# Tally_v01.net
KiCad netlist of a schematic drawn in EAGLE
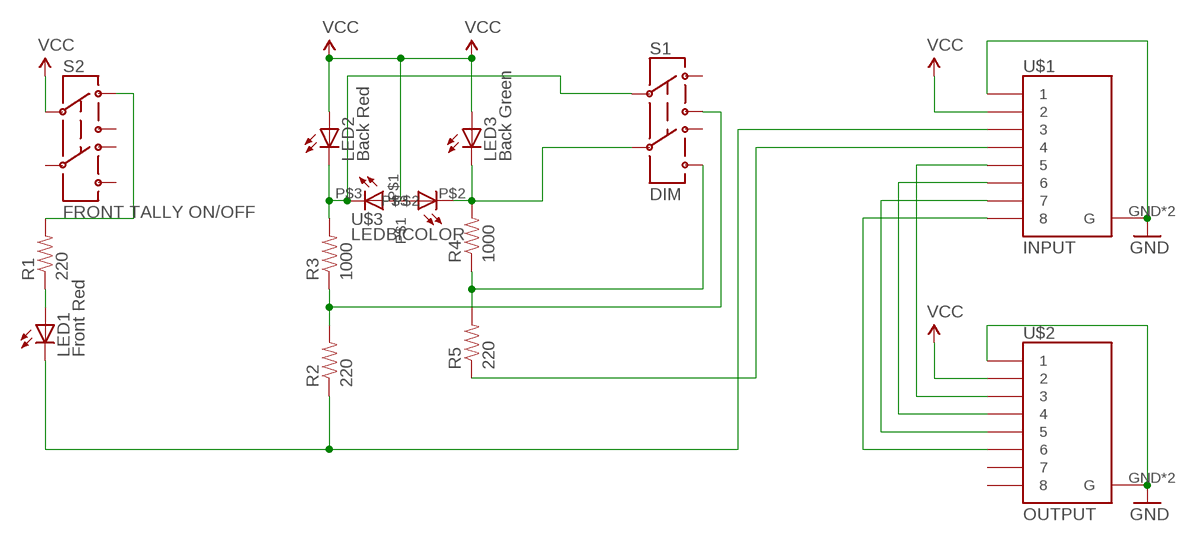
[diagram p0: schematic, sheet 1]

(export (version "E")
  (design (tool "Eeschema 10.0.6"))
  (components
    (comp (ref "LED1")
      (value "Front Red")
      (footprint "eagle-import:LED20")
      (libsource (lib "eagle-import") (part "LED20"))
    )
    (comp (ref "LED2")
      (value "Back Red")
      (footprint "eagle-import:LED20")
      (libsource (lib "eagle-import") (part "LED20"))
    )
    (comp (ref "LED3")
      (value "Back Green")
      (footprint "eagle-import:LED20")
      (libsource (lib "eagle-import") (part "LED20"))
    )
    (comp (ref "R1")
      (value "220")
      (footprint "eagle-import:AXIAL-0.4")
      (libsource (lib "eagle-import") (part "RESISTORPTH-1/4W"))
    )
    (comp (ref "R2")
      (value "220")
      (footprint "eagle-import:AXIAL-0.4")
      (libsource (lib "eagle-import") (part "RESISTORPTH-1/4W"))
    )
    (comp (ref "R3")
      (value "1000")
      (footprint "eagle-import:AXIAL-0.4")
      (libsource (lib "eagle-import") (part "RESISTORPTH-1/4W"))
    )
    (comp (ref "R4")
      (value "1000")
      (footprint "eagle-import:AXIAL-0.4")
      (libsource (lib "eagle-import") (part "RESISTORPTH-1/4W"))
    )
    (comp (ref "R5")
      (value "220")
      (footprint "eagle-import:AXIAL-0.4")
      (libsource (lib "eagle-import") (part "RESISTORPTH-1/4W"))
    )
    (comp (ref "S1")
      (value "DIM")
      (footprint "eagle-import:TECONNECTIVITY-DPDT")
      (libsource (lib "eagle-import") (part "SWITCH-DPDTPTH1"))
    )
    (comp (ref "S2")
      (value "FRONT TALLY ON/OFF")
      (footprint "eagle-import:TECONNECTIVITY-DPDT")
      (libsource (lib "eagle-import") (part "SWITCH-DPDTPTH1"))
    )
    (comp (ref "U$1")
      (value "INPUT")
      (footprint "eagle-import:RJ45-8_GND")
      (libsource (lib "eagle-import") (part "RJ45-8_GND"))
    )
    (comp (ref "U$2")
      (value "OUTPUT")
      (footprint "eagle-import:RJ45-8_GND")
      (libsource (lib "eagle-import") (part "RJ45-8_GND"))
    )
    (comp (ref "U$3")
      (value "LEDBICOLOR")
      (footprint "eagle-import:LEDBICOLOR")
      (libsource (lib "eagle-import") (part "LEDBICOLOR"))
    )
  )
  (nets
    (net (code "1") (name "GND") (class "Default")
      (node (ref "U$1") (pin "1") (pinfunction "1_1") (pintype "bidirectional"))
      (node (ref "U$1") (pin "GND") (pinfunction "G_GND") (pintype "power_in"))
      (node (ref "U$1") (pin "GND1") (pinfunction "G_GND1") (pintype "power_in"))
      (node (ref "U$2") (pin "1") (pinfunction "1_1") (pintype "bidirectional"))
      (node (ref "U$2") (pin "GND") (pinfunction "G_GND") (pintype "power_in"))
      (node (ref "U$2") (pin "GND1") (pinfunction "G_GND1") (pintype "power_in"))
    )
    (net (code "2") (name "Net-(LED1-A)") (class "Default")
      (node (ref "LED1") (pin "P$1") (pinfunction "A_P$1") (pintype "passive"))
      (node (ref "R1") (pin "P$1") (pinfunction "1_P$1") (pintype "passive"))
    )
    (net (code "3") (name "Net-(LED1-C)") (class "Default")
      (node (ref "LED1") (pin "P$2") (pinfunction "C_P$2") (pintype "passive"))
      (node (ref "R2") (pin "P$1") (pinfunction "1_P$1") (pintype "passive"))
      (node (ref "U$1") (pin "3") (pinfunction "3_3") (pintype "bidirectional"))
    )
    (net (code "4") (name "Net-(LED2-C)") (class "Default")
      (node (ref "LED2") (pin "P$2") (pinfunction "C_P$2") (pintype "passive"))
      (node (ref "R3") (pin "P$2") (pinfunction "2_P$2") (pintype "passive"))
      (node (ref "S1") (pin "P$2") (pinfunction "2_P$2") (pintype "bidirectional"))
      (node (ref "U$3") (pin "P$3") (pinfunction "P$3_P$3") (pintype "bidirectional"))
    )
    (net (code "5") (name "Net-(LED3-C)") (class "Default")
      (node (ref "LED3") (pin "P$2") (pinfunction "C_P$2") (pintype "passive"))
      (node (ref "R4") (pin "P$2") (pinfunction "2_P$2") (pintype "passive"))
      (node (ref "S1") (pin "P$5") (pinfunction "5_P$5") (pintype "bidirectional"))
      (node (ref "U$3") (pin "P$2") (pinfunction "P$2_P$2") (pintype "bidirectional"))
    )
    (net (code "6") (name "Net-(R1-2)") (class "Default")
      (node (ref "R1") (pin "P$2") (pinfunction "2_P$2") (pintype "passive"))
      (node (ref "S2") (pin "P$1") (pinfunction "1_P$1") (pintype "bidirectional"))
    )
    (net (code "7") (name "Net-(R2-2)") (class "Default")
      (node (ref "R2") (pin "P$2") (pinfunction "2_P$2") (pintype "passive"))
      (node (ref "R3") (pin "P$1") (pinfunction "1_P$1") (pintype "passive"))
      (node (ref "S1") (pin "P$3") (pinfunction "3_P$3") (pintype "bidirectional"))
    )
    (net (code "8") (name "Net-(R4-1)") (class "Default")
      (node (ref "R4") (pin "P$1") (pinfunction "1_P$1") (pintype "passive"))
      (node (ref "R5") (pin "P$2") (pinfunction "2_P$2") (pintype "passive"))
      (node (ref "S1") (pin "P$6") (pinfunction "6_P$6") (pintype "bidirectional"))
    )
    (net (code "9") (name "Net-(R5-1)") (class "Default")
      (node (ref "R5") (pin "P$1") (pinfunction "1_P$1") (pintype "passive"))
      (node (ref "U$1") (pin "4") (pinfunction "4_4") (pintype "bidirectional"))
    )
    (net (code "10") (name "Net-(U$1-Pad5)") (class "Default")
      (node (ref "U$1") (pin "5") (pinfunction "5_5") (pintype "bidirectional"))
      (node (ref "U$2") (pin "3") (pinfunction "3_3") (pintype "bidirectional"))
    )
    (net (code "11") (name "Net-(U$1-Pad6)") (class "Default")
      (node (ref "U$1") (pin "6") (pinfunction "6_6") (pintype "bidirectional"))
      (node (ref "U$2") (pin "4") (pinfunction "4_4") (pintype "bidirectional"))
    )
    (net (code "12") (name "Net-(U$1-Pad7)") (class "Default")
      (node (ref "U$1") (pin "7") (pinfunction "7_7") (pintype "bidirectional"))
      (node (ref "U$2") (pin "5") (pinfunction "5_5") (pintype "bidirectional"))
    )
    (net (code "13") (name "Net-(U$1-Pad8)") (class "Default")
      (node (ref "U$1") (pin "8") (pinfunction "8_8") (pintype "bidirectional"))
      (node (ref "U$2") (pin "6") (pinfunction "6_6") (pintype "bidirectional"))
    )
    (net (code "14") (name "VCC") (class "Default")
      (node (ref "LED2") (pin "P$1") (pinfunction "A_P$1") (pintype "passive"))
      (node (ref "LED3") (pin "P$1") (pinfunction "A_P$1") (pintype "passive"))
      (node (ref "S2") (pin "P$2") (pinfunction "2_P$2") (pintype "bidirectional"))
      (node (ref "U$1") (pin "2") (pinfunction "2_2") (pintype "bidirectional"))
      (node (ref "U$2") (pin "2") (pinfunction "2_2") (pintype "bidirectional"))
      (node (ref "U$3") (pin "P$1") (pinfunction "P$1_P$1") (pintype "bidirectional"))
    )
    (net (code "15") (name "unconnected-(S1-1-PadP$1)") (class "Default")
      (node (ref "S1") (pin "P$1") (pinfunction "1_P$1") (pintype "bidirectional"))
    )
    (net (code "16") (name "unconnected-(S1-4-PadP$4)") (class "Default")
      (node (ref "S1") (pin "P$4") (pinfunction "4_P$4") (pintype "bidirectional"))
    )
    (net (code "17") (name "unconnected-(S2-3-PadP$3)") (class "Default")
      (node (ref "S2") (pin "P$3") (pinfunction "3_P$3") (pintype "bidirectional"))
    )
    (net (code "18") (name "unconnected-(S2-4-PadP$4)") (class "Default")
      (node (ref "S2") (pin "P$4") (pinfunction "4_P$4") (pintype "bidirectional"))
    )
    (net (code "19") (name "unconnected-(S2-5-PadP$5)") (class "Default")
      (node (ref "S2") (pin "P$5") (pinfunction "5_P$5") (pintype "bidirectional"))
    )
    (net (code "20") (name "unconnected-(S2-6-PadP$6)") (class "Default")
      (node (ref "S2") (pin "P$6") (pinfunction "6_P$6") (pintype "bidirectional"))
    )
    (net (code "21") (name "unconnected-(U$2-Pad7)") (class "Default")
      (node (ref "U$2") (pin "7") (pinfunction "7_7") (pintype "bidirectional"))
    )
    (net (code "22") (name "unconnected-(U$2-Pad8)") (class "Default")
      (node (ref "U$2") (pin "8") (pinfunction "8_8") (pintype "bidirectional"))
    )
  )
)
